# old_Debug.net
KiCad netlist of a schematic drawn in Altium Designer
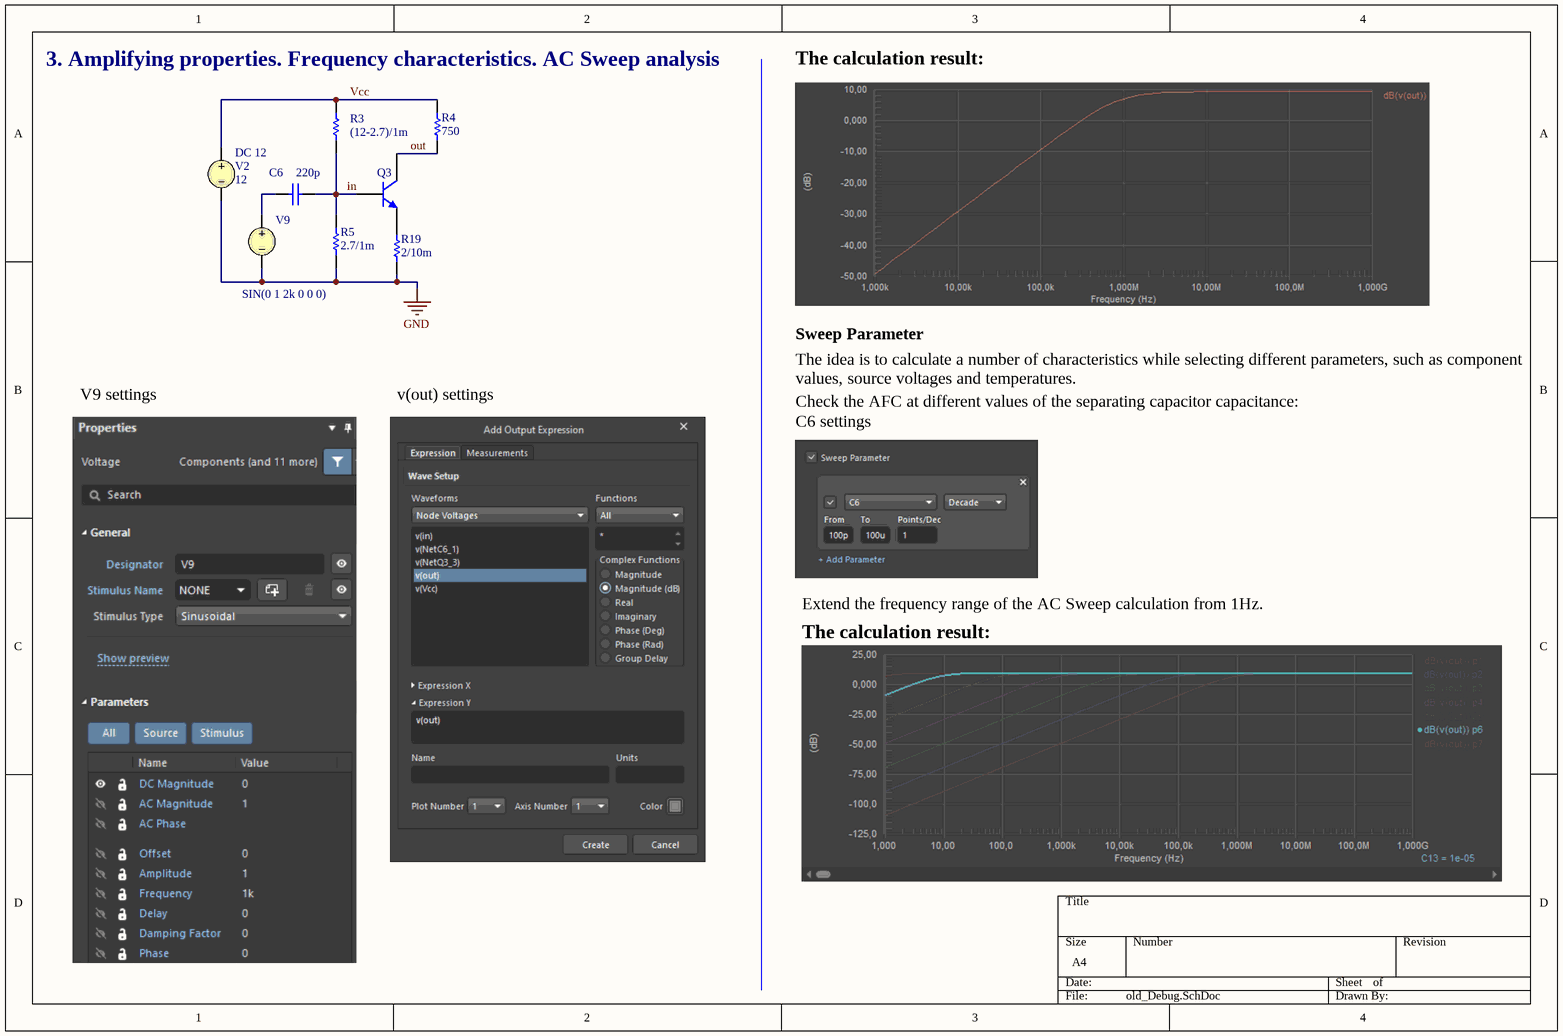
[diagram p0: old_Debug.SchDoc]

(export (version "E")
  (design (tool "Eeschema 10.0.6"))
  (components
    (comp (ref "C6")
      (value "220p")
      (description "Capacitor")
      (libsource (lib "Simulation Generic Components") (part "Capacitor"))
    )
    (comp (ref "Q3")
      (value "Bipolar  NPN 3 Pins  Transistor  Modified Version of the Gummel-Poon Model")
      (libsource (lib "Simulation Generic Components") (part "BJT NPN_MGP"))
    )
    (comp (ref "R3")
      (value "(12-2.7)/1m")
      (description "Resistor")
      (libsource (lib "Simulation Generic Components") (part "Resistor"))
    )
    (comp (ref "R4")
      (value "750")
      (description "Resistor")
      (libsource (lib "Simulation Generic Components") (part "Resistor"))
    )
    (comp (ref "R5")
      (value "2.7/1m")
      (description "Resistor")
      (libsource (lib "Simulation Generic Components") (part "Resistor"))
    )
    (comp (ref "R19")
      (value "2/10m")
      (description "Resistor")
      (libsource (lib "Simulation Generic Components") (part "Resistor"))
    )
    (comp (ref "V2")
      (value "DC 12")
      (description "Voltage Source")
      (fields (field (name "ALTIUM_VALUE") "12") (field (name "PUBLISHER") "Altium Limited"))
      (libsource (lib "Simulation Generic Components") (part "VSRC"))
    )
    (comp (ref "V9")
      (value "SIN(0 1 2k 0 0 0)")
      (description "Voltage Source")
      (fields (field (name "PUBLISHER") "Altium Limited"))
      (libsource (lib "Simulation Generic Components") (part "VSRC"))
    )
  )
  (nets
    (net (code "1") (name "/Vcc") (class "Default")
      (node (ref "R3") (pin "2") (pinfunction "2_2") (pintype "passive"))
      (node (ref "R4") (pin "2") (pinfunction "2_2") (pintype "passive"))
      (node (ref "V2") (pin "1") (pinfunction "1_1") (pintype "passive"))
    )
    (net (code "2") (name "/in") (class "Default")
      (node (ref "C6") (pin "2") (pinfunction "2_2") (pintype "passive"))
      (node (ref "Q3") (pin "2") (pinfunction "B_2") (pintype "passive"))
      (node (ref "R3") (pin "1") (pinfunction "1_1") (pintype "passive"))
      (node (ref "R5") (pin "1") (pinfunction "1_1") (pintype "passive"))
    )
    (net (code "3") (name "/out") (class "Default")
      (node (ref "Q3") (pin "1") (pinfunction "C_1") (pintype "passive"))
      (node (ref "R4") (pin "1") (pinfunction "1_1") (pintype "passive"))
    )
    (net (code "4") (name "GND") (class "Default")
      (node (ref "R19") (pin "1") (pinfunction "1_1") (pintype "passive"))
      (node (ref "R5") (pin "2") (pinfunction "2_2") (pintype "passive"))
      (node (ref "V2") (pin "2") (pinfunction "2_2") (pintype "passive"))
      (node (ref "V9") (pin "2") (pinfunction "2_2") (pintype "passive"))
    )
    (net (code "5") (name "Net-(C6-Pad1)") (class "Default")
      (node (ref "C6") (pin "1") (pinfunction "1_1") (pintype "passive"))
      (node (ref "V9") (pin "1") (pinfunction "1_1") (pintype "passive"))
    )
    (net (code "6") (name "Net-(Q3-E)") (class "Default")
      (node (ref "Q3") (pin "3") (pinfunction "E_3") (pintype "passive"))
      (node (ref "R19") (pin "2") (pinfunction "2_2") (pintype "passive"))
    )
  )
)
